# adsr2.net
KiCad netlist of a schematic drawn in EAGLE
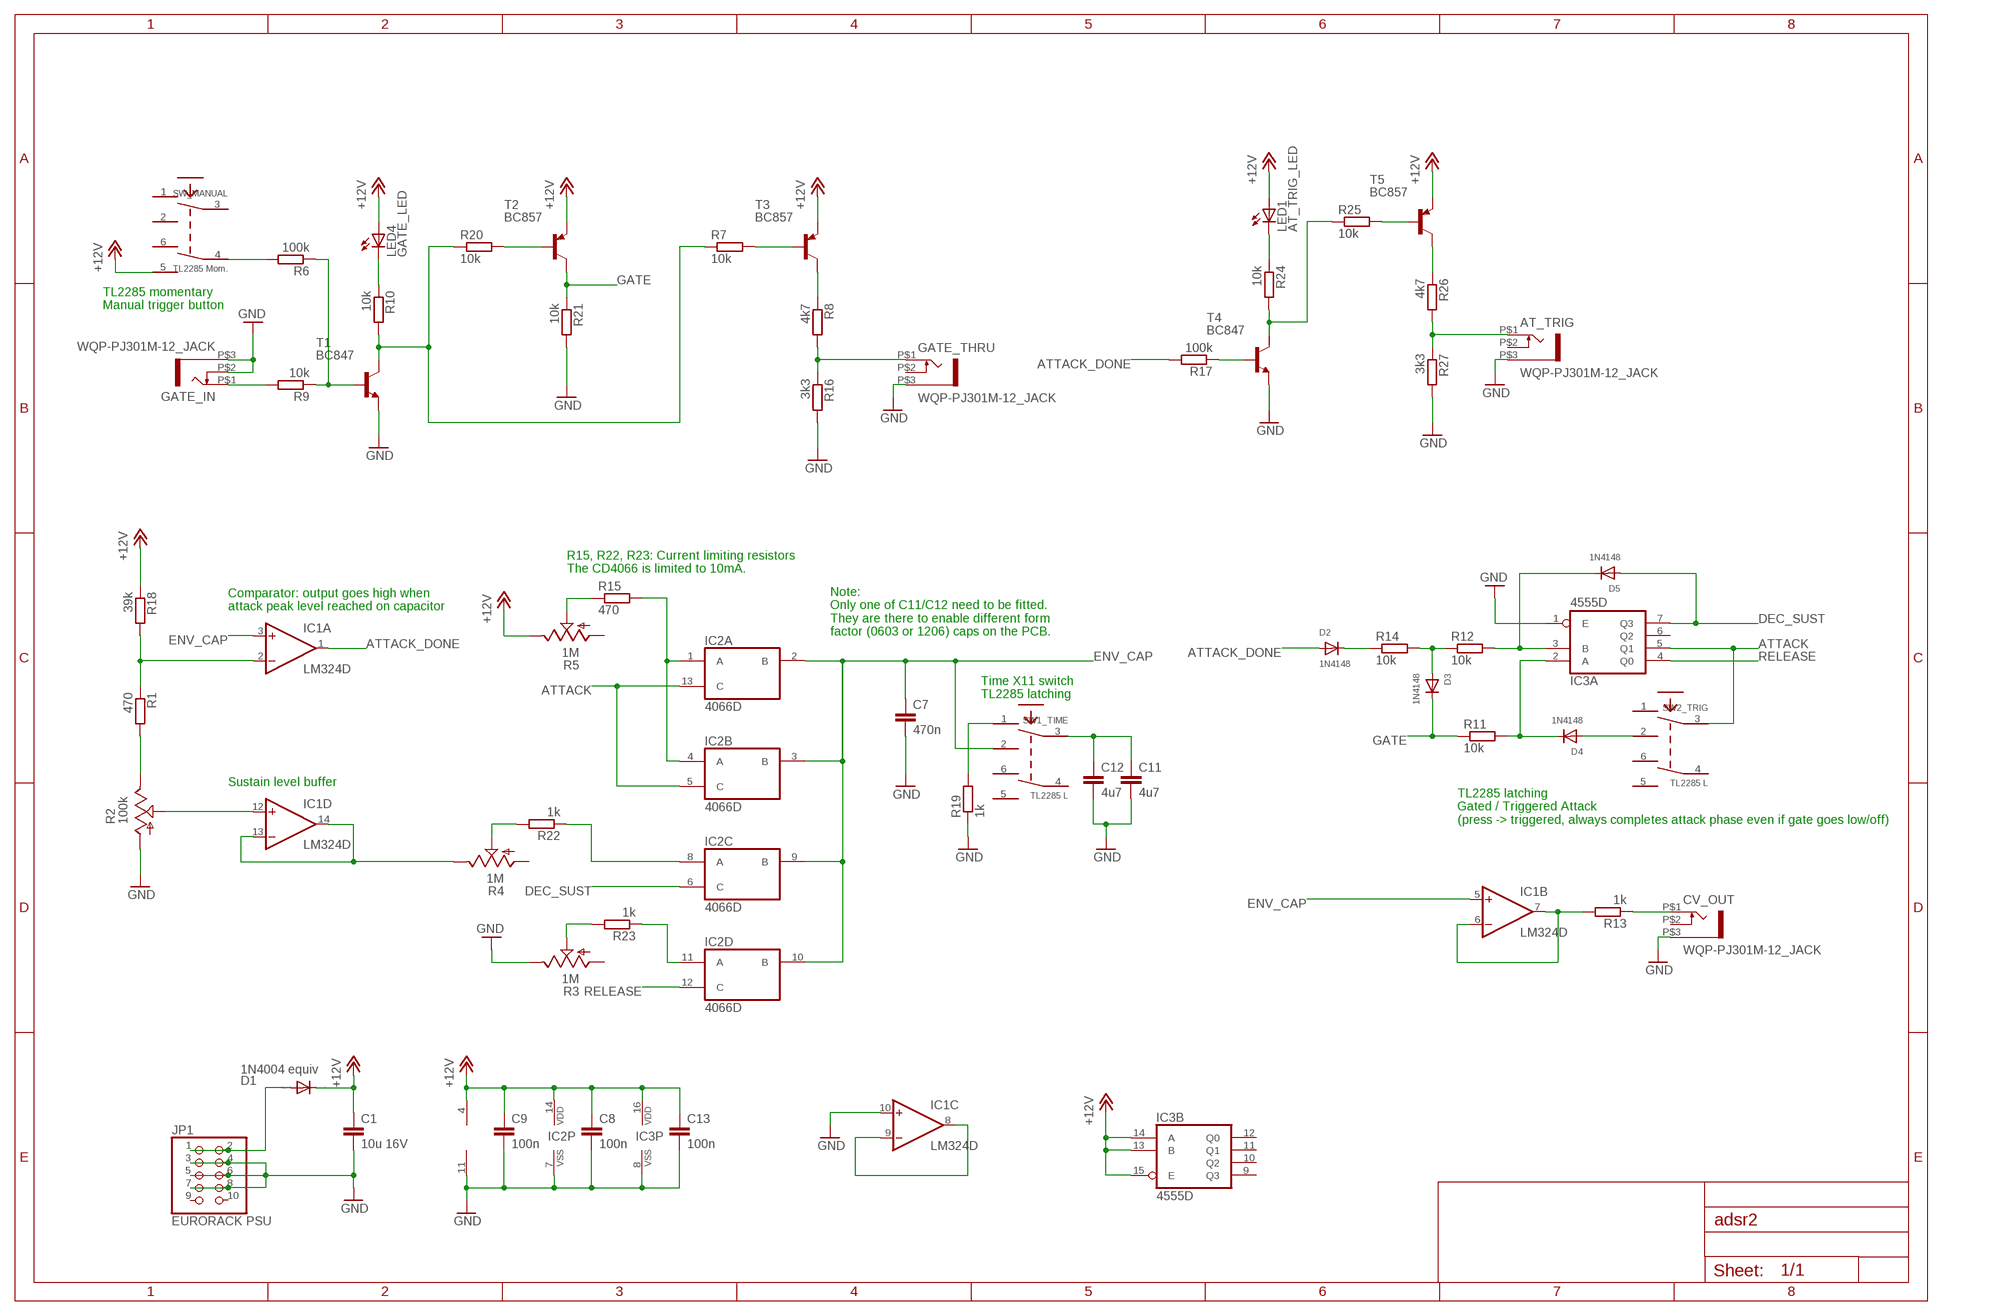
[diagram p0: schematic, sheet 1]

(export (version "E")
  (design (tool "Eeschema 10.0.6"))
  (components
    (comp (ref "AT_TRIG")
      (value "WQP-PJ301M-12_JACK")
      (footprint "eagle-import:WQP-PJ301M-12_JACK")
      (libsource (lib "eagle-import") (part "WQP-PJ301M-12_JACK"))
    )
    (comp (ref "C1")
      (value "10u 16V")
      (footprint "eagle-import:C1206K")
      (libsource (lib "eagle-import") (part "C-EUC1206K"))
    )
    (comp (ref "C7")
      (value "470n")
      (footprint "eagle-import:C0603K")
      (libsource (lib "eagle-import") (part "C-EUC0603K"))
    )
    (comp (ref "C8")
      (value "100n")
      (footprint "eagle-import:C0603K")
      (libsource (lib "eagle-import") (part "C-EUC0603K"))
    )
    (comp (ref "C9")
      (value "100n")
      (footprint "eagle-import:C0603K")
      (libsource (lib "eagle-import") (part "C-EUC0603K"))
    )
    (comp (ref "C11")
      (value "4u7")
      (footprint "eagle-import:C1206K")
      (libsource (lib "eagle-import") (part "C-EUC1206K"))
    )
    (comp (ref "C12")
      (value "4u7")
      (footprint "eagle-import:C0603K")
      (libsource (lib "eagle-import") (part "C-EUC0603K"))
    )
    (comp (ref "C13")
      (value "100n")
      (footprint "eagle-import:C0603K")
      (libsource (lib "eagle-import") (part "C-EUC0603K"))
    )
    (comp (ref "CV_OUT")
      (value "WQP-PJ301M-12_JACK")
      (footprint "eagle-import:WQP-PJ301M-12_JACK")
      (libsource (lib "eagle-import") (part "WQP-PJ301M-12_JACK"))
    )
    (comp (ref "D1")
      (value "1N4004 equiv")
      (footprint "eagle-import:DO214AA")
      (libsource (lib "eagle-import") (part "DIODE-DO214AA"))
    )
    (comp (ref "D2")
      (value "1N4148")
      (footprint "eagle-import:SOD-323F")
      (libsource (lib "eagle-import") (part "DIODESOD-323F"))
    )
    (comp (ref "D3")
      (value "1N4148")
      (footprint "eagle-import:SOD-323F")
      (libsource (lib "eagle-import") (part "DIODESOD-323F"))
    )
    (comp (ref "D4")
      (value "1N4148")
      (footprint "eagle-import:SOD-323F")
      (libsource (lib "eagle-import") (part "DIODESOD-323F"))
    )
    (comp (ref "D5")
      (value "1N4148")
      (footprint "eagle-import:SOD-323F")
      (libsource (lib "eagle-import") (part "DIODESOD-323F"))
    )
    (comp (ref "GATE_IN")
      (value "WQP-PJ301M-12_JACK")
      (footprint "eagle-import:WQP-PJ301M-12_JACK")
      (libsource (lib "eagle-import") (part "WQP-PJ301M-12_JACK"))
    )
    (comp (ref "GATE_THRU")
      (value "WQP-PJ301M-12_JACK")
      (footprint "eagle-import:WQP-PJ301M-12_JACK")
      (libsource (lib "eagle-import") (part "WQP-PJ301M-12_JACK"))
    )
    (comp (ref "IC1")
      (value "LM324D")
      (footprint "eagle-import:SO14")
      (libsource (lib "eagle-import") (part "LM324D"))
    )
    (comp (ref "IC2")
      (value "4066D")
      (footprint "eagle-import:SO14")
      (libsource (lib "eagle-import") (part "4066D"))
    )
    (comp (ref "IC3")
      (value "4555D")
      (footprint "eagle-import:SO16")
      (libsource (lib "eagle-import") (part "4555D"))
    )
    (comp (ref "JP1")
      (value "EURORACK PSU")
      (footprint "eagle-import:2X05")
      (libsource (lib "eagle-import") (part "PINHD-2X5"))
    )
    (comp (ref "LED1")
      (value "AT_TRIG_LED")
      (footprint "eagle-import:LED3MM")
      (libsource (lib "eagle-import") (part "LED3MM"))
    )
    (comp (ref "LED4")
      (value "GATE_LED")
      (footprint "eagle-import:LED3MM")
      (libsource (lib "eagle-import") (part "LED3MM"))
    )
    (comp (ref "R1")
      (value "470")
      (footprint "eagle-import:R0603")
      (libsource (lib "eagle-import") (part "R-EU_R0603"))
    )
    (comp (ref "R2")
      (value "100k")
      (footprint "eagle-import:ALPS_POT_VERTICAL")
      (libsource (lib "eagle-import") (part "POT_USVERTICAL"))
    )
    (comp (ref "R3")
      (value "1M")
      (footprint "eagle-import:ALPS_POT_VERTICAL")
      (libsource (lib "eagle-import") (part "POT_USVERTICAL"))
    )
    (comp (ref "R4")
      (value "1M")
      (footprint "eagle-import:ALPS_POT_VERTICAL")
      (libsource (lib "eagle-import") (part "POT_USVERTICAL"))
    )
    (comp (ref "R5")
      (value "1M")
      (footprint "eagle-import:ALPS_POT_VERTICAL")
      (libsource (lib "eagle-import") (part "POT_USVERTICAL"))
    )
    (comp (ref "R6")
      (value "100k")
      (footprint "eagle-import:R0603")
      (libsource (lib "eagle-import") (part "R-EU_R0603"))
    )
    (comp (ref "R7")
      (value "10k")
      (footprint "eagle-import:R0603")
      (libsource (lib "eagle-import") (part "R-EU_R0603"))
    )
    (comp (ref "R8")
      (value "4k7")
      (footprint "eagle-import:R0603")
      (libsource (lib "eagle-import") (part "R-EU_R0603"))
    )
    (comp (ref "R9")
      (value "10k")
      (footprint "eagle-import:R0603")
      (libsource (lib "eagle-import") (part "R-EU_R0603"))
    )
    (comp (ref "R10")
      (value "10k")
      (footprint "eagle-import:R0603")
      (libsource (lib "eagle-import") (part "R-EU_R0603"))
    )
    (comp (ref "R11")
      (value "10k")
      (footprint "eagle-import:R0603")
      (libsource (lib "eagle-import") (part "R-EU_R0603"))
    )
    (comp (ref "R12")
      (value "10k")
      (footprint "eagle-import:R0603")
      (libsource (lib "eagle-import") (part "R-EU_R0603"))
    )
    (comp (ref "R13")
      (value "1k")
      (footprint "eagle-import:R0603")
      (libsource (lib "eagle-import") (part "R-EU_R0603"))
    )
    (comp (ref "R14")
      (value "10k")
      (footprint "eagle-import:R0603")
      (libsource (lib "eagle-import") (part "R-EU_R0603"))
    )
    (comp (ref "R15")
      (value "470")
      (footprint "eagle-import:R0603")
      (libsource (lib "eagle-import") (part "R-EU_R0603"))
    )
    (comp (ref "R16")
      (value "3k3")
      (footprint "eagle-import:R0603")
      (libsource (lib "eagle-import") (part "R-EU_R0603"))
    )
    (comp (ref "R17")
      (value "100k")
      (footprint "eagle-import:R0603")
      (libsource (lib "eagle-import") (part "R-EU_R0603"))
    )
    (comp (ref "R18")
      (value "39k")
      (footprint "eagle-import:R0603")
      (libsource (lib "eagle-import") (part "R-EU_R0603"))
    )
    (comp (ref "R19")
      (value "1k")
      (footprint "eagle-import:R0603")
      (libsource (lib "eagle-import") (part "R-EU_R0603"))
    )
    (comp (ref "R20")
      (value "10k")
      (footprint "eagle-import:R0603")
      (libsource (lib "eagle-import") (part "R-EU_R0603"))
    )
    (comp (ref "R21")
      (value "10k")
      (footprint "eagle-import:R0603")
      (libsource (lib "eagle-import") (part "R-EU_R0603"))
    )
    (comp (ref "R22")
      (value "1k")
      (footprint "eagle-import:R0603")
      (libsource (lib "eagle-import") (part "R-EU_R0603"))
    )
    (comp (ref "R23")
      (value "1k")
      (footprint "eagle-import:R0603")
      (libsource (lib "eagle-import") (part "R-EU_R0603"))
    )
    (comp (ref "R24")
      (value "10k")
      (footprint "eagle-import:R0603")
      (libsource (lib "eagle-import") (part "R-EU_R0603"))
    )
    (comp (ref "R25")
      (value "10k")
      (footprint "eagle-import:R0603")
      (libsource (lib "eagle-import") (part "R-EU_R0603"))
    )
    (comp (ref "R26")
      (value "4k7")
      (footprint "eagle-import:R0603")
      (libsource (lib "eagle-import") (part "R-EU_R0603"))
    )
    (comp (ref "R27")
      (value "3k3")
      (footprint "eagle-import:R0603")
      (libsource (lib "eagle-import") (part "R-EU_R0603"))
    )
    (comp (ref "SW1_TIME")
      (value "TL2285 L")
      (footprint "eagle-import:TL2285_PCB")
      (libsource (lib "eagle-import") (part "TL2285"))
    )
    (comp (ref "SW2_TRIG")
      (value "TL2285 L")
      (footprint "eagle-import:TL2285_PCB")
      (libsource (lib "eagle-import") (part "TL2285"))
    )
    (comp (ref "SW_MANUAL")
      (value "TL2285 Mom.")
      (footprint "eagle-import:TL2285_PCB")
      (libsource (lib "eagle-import") (part "TL2285"))
    )
    (comp (ref "T1")
      (value "BC847")
      (footprint "eagle-import:SOT23")
      (libsource (lib "eagle-import") (part "BC847"))
    )
    (comp (ref "T2")
      (value "BC857")
      (footprint "eagle-import:SOT23-BEC")
      (libsource (lib "eagle-import") (part "-PNP-SOT23-BECBC857A"))
    )
    (comp (ref "T3")
      (value "BC857")
      (footprint "eagle-import:SOT23-BEC")
      (libsource (lib "eagle-import") (part "-PNP-SOT23-BECBC857A"))
    )
    (comp (ref "T4")
      (value "BC847")
      (footprint "eagle-import:SOT23")
      (libsource (lib "eagle-import") (part "BC847"))
    )
    (comp (ref "T5")
      (value "BC857")
      (footprint "eagle-import:SOT23-BEC")
      (libsource (lib "eagle-import") (part "-PNP-SOT23-BECBC857A"))
    )
  )
  (nets
    (net (code "1") (name "+12V") (class "Default")
      (node (ref "C1") (pin "1") (pinfunction "1_1") (pintype "passive"))
      (node (ref "C13") (pin "1") (pinfunction "1_1") (pintype "passive"))
      (node (ref "C8") (pin "1") (pinfunction "1_1") (pintype "passive"))
      (node (ref "C9") (pin "1") (pinfunction "1_1") (pintype "passive"))
      (node (ref "D1") (pin "C") (pinfunction "C_C") (pintype "passive"))
      (node (ref "IC1") (pin "4") (pinfunction "V+_4") (pintype "power_in"))
      (node (ref "IC2") (pin "14") (pinfunction "VDD_14") (pintype "power_in"))
      (node (ref "IC3") (pin "13") (pinfunction "B_13") (pintype "input"))
      (node (ref "IC3") (pin "14") (pinfunction "A_14") (pintype "input"))
      (node (ref "IC3") (pin "15") (pinfunction "E_15") (pintype "input"))
      (node (ref "IC3") (pin "16") (pinfunction "VDD_16") (pintype "power_in"))
      (node (ref "LED1") (pin "A") (pinfunction "A_A") (pintype "passive"))
      (node (ref "LED4") (pin "A") (pinfunction "A_A") (pintype "passive"))
      (node (ref "R18") (pin "1") (pinfunction "1_1") (pintype "passive"))
      (node (ref "R5") (pin "P$1") (pinfunction "E_P$1") (pintype "passive"))
      (node (ref "SW_MANUAL") (pin "5") (pinfunction "P5_5") (pintype "bidirectional"))
      (node (ref "T2") (pin "E") (pinfunction "E_E") (pintype "passive"))
      (node (ref "T3") (pin "E") (pinfunction "E_E") (pintype "passive"))
      (node (ref "T5") (pin "E") (pinfunction "E_E") (pintype "passive"))
    )
    (net (code "2") (name "/ATTACK") (class "Default")
      (node (ref "IC2") (pin "13") (pinfunction "C_13") (pintype "input"))
      (node (ref "IC2") (pin "5") (pinfunction "C_5") (pintype "input"))
      (node (ref "IC3") (pin "5") (pinfunction "Q1_5") (pintype "output"))
      (node (ref "SW2_TRIG") (pin "3") (pinfunction "P3_3") (pintype "bidirectional"))
    )
    (net (code "3") (name "/ATTACK_DONE") (class "Default")
      (node (ref "D2") (pin "A") (pinfunction "A_A") (pintype "passive"))
      (node (ref "IC1") (pin "1") (pinfunction "OUT_1") (pintype "output"))
      (node (ref "R17") (pin "2") (pinfunction "2_2") (pintype "passive"))
    )
    (net (code "4") (name "/DEC_SUST") (class "Default")
      (node (ref "D5") (pin "A") (pinfunction "A_A") (pintype "passive"))
      (node (ref "IC2") (pin "6") (pinfunction "C_6") (pintype "input"))
      (node (ref "IC3") (pin "7") (pinfunction "Q3_7") (pintype "output"))
    )
    (net (code "5") (name "/ENV_CAP") (class "Default")
      (node (ref "C7") (pin "1") (pinfunction "1_1") (pintype "passive"))
      (node (ref "IC1") (pin "3") (pinfunction "+IN_3") (pintype "input"))
      (node (ref "IC1") (pin "5") (pinfunction "+IN_5") (pintype "input"))
      (node (ref "IC2") (pin "10") (pinfunction "B_10") (pintype "tri_state"))
      (node (ref "IC2") (pin "2") (pinfunction "B_2") (pintype "tri_state"))
      (node (ref "IC2") (pin "3") (pinfunction "B_3") (pintype "tri_state"))
      (node (ref "IC2") (pin "9") (pinfunction "B_9") (pintype "tri_state"))
      (node (ref "SW1_TIME") (pin "2") (pinfunction "P2_2") (pintype "bidirectional"))
    )
    (net (code "6") (name "/GATE") (class "Default")
      (node (ref "D3") (pin "C") (pinfunction "C_C") (pintype "passive"))
      (node (ref "R11") (pin "1") (pinfunction "1_1") (pintype "passive"))
      (node (ref "R21") (pin "1") (pinfunction "1_1") (pintype "passive"))
      (node (ref "T2") (pin "C") (pinfunction "C_C") (pintype "passive"))
    )
    (net (code "7") (name "/RELEASE") (class "Default")
      (node (ref "IC2") (pin "12") (pinfunction "C_12") (pintype "input"))
      (node (ref "IC3") (pin "4") (pinfunction "Q0_4") (pintype "output"))
    )
    (net (code "8") (name "GND") (class "Default")
      (node (ref "AT_TRIG") (pin "P$3") (pinfunction "1_P$3") (pintype "passive"))
      (node (ref "C1") (pin "2") (pinfunction "2_2") (pintype "passive"))
      (node (ref "C11") (pin "2") (pinfunction "2_2") (pintype "passive"))
      (node (ref "C12") (pin "2") (pinfunction "2_2") (pintype "passive"))
      (node (ref "C13") (pin "2") (pinfunction "2_2") (pintype "passive"))
      (node (ref "C7") (pin "2") (pinfunction "2_2") (pintype "passive"))
      (node (ref "C8") (pin "2") (pinfunction "2_2") (pintype "passive"))
      (node (ref "C9") (pin "2") (pinfunction "2_2") (pintype "passive"))
      (node (ref "CV_OUT") (pin "P$3") (pinfunction "1_P$3") (pintype "passive"))
      (node (ref "GATE_IN") (pin "P$2") (pinfunction "3_P$2") (pintype "passive"))
      (node (ref "GATE_IN") (pin "P$3") (pinfunction "1_P$3") (pintype "passive"))
      (node (ref "GATE_THRU") (pin "P$3") (pinfunction "1_P$3") (pintype "passive"))
      (node (ref "IC1") (pin "10") (pinfunction "+IN_10") (pintype "input"))
      (node (ref "IC1") (pin "11") (pinfunction "V-_11") (pintype "power_in"))
      (node (ref "IC2") (pin "7") (pinfunction "VSS_7") (pintype "power_in"))
      (node (ref "IC3") (pin "1") (pinfunction "E_1") (pintype "input"))
      (node (ref "IC3") (pin "8") (pinfunction "VSS_8") (pintype "power_in"))
      (node (ref "JP1") (pin "3") (pinfunction "3_3") (pintype "passive"))
      (node (ref "JP1") (pin "4") (pinfunction "4_4") (pintype "passive"))
      (node (ref "JP1") (pin "5") (pinfunction "5_5") (pintype "passive"))
      (node (ref "JP1") (pin "6") (pinfunction "6_6") (pintype "passive"))
      (node (ref "JP1") (pin "7") (pinfunction "7_7") (pintype "passive"))
      (node (ref "JP1") (pin "8") (pinfunction "8_8") (pintype "passive"))
      (node (ref "R16") (pin "2") (pinfunction "2_2") (pintype "passive"))
      (node (ref "R19") (pin "1") (pinfunction "1_1") (pintype "passive"))
      (node (ref "R2") (pin "P$3") (pinfunction "A_P$3") (pintype "passive"))
      (node (ref "R21") (pin "2") (pinfunction "2_2") (pintype "passive"))
      (node (ref "R27") (pin "2") (pinfunction "2_2") (pintype "passive"))
      (node (ref "R3") (pin "P$1") (pinfunction "E_P$1") (pintype "passive"))
      (node (ref "T1") (pin "2") (pinfunction "E_2") (pintype "passive"))
      (node (ref "T4") (pin "2") (pinfunction "E_2") (pintype "passive"))
    )
    (net (code "9") (name "Net-(AT_TRIG-2)") (class "Default")
      (node (ref "AT_TRIG") (pin "P$1") (pinfunction "2_P$1") (pintype "passive"))
      (node (ref "R26") (pin "2") (pinfunction "2_2") (pintype "passive"))
      (node (ref "R27") (pin "1") (pinfunction "1_1") (pintype "passive"))
    )
    (net (code "10") (name "Net-(CV_OUT-2)") (class "Default")
      (node (ref "CV_OUT") (pin "P$1") (pinfunction "2_P$1") (pintype "passive"))
      (node (ref "R13") (pin "1") (pinfunction "1_1") (pintype "passive"))
    )
    (net (code "11") (name "Net-(D1-PadA)") (class "Default")
      (node (ref "D1") (pin "A") (pinfunction "A_A") (pintype "passive"))
      (node (ref "JP1") (pin "1") (pinfunction "1_1") (pintype "passive"))
      (node (ref "JP1") (pin "2") (pinfunction "2_2") (pintype "passive"))
    )
    (net (code "12") (name "Net-(D2-PadC)") (class "Default")
      (node (ref "D2") (pin "C") (pinfunction "C_C") (pintype "passive"))
      (node (ref "R14") (pin "1") (pinfunction "1_1") (pintype "passive"))
    )
    (net (code "13") (name "Net-(D3-PadA)") (class "Default")
      (node (ref "D3") (pin "A") (pinfunction "A_A") (pintype "passive"))
      (node (ref "R12") (pin "1") (pinfunction "1_1") (pintype "passive"))
      (node (ref "R14") (pin "2") (pinfunction "2_2") (pintype "passive"))
    )
    (net (code "14") (name "Net-(GATE_IN-2)") (class "Default")
      (node (ref "GATE_IN") (pin "P$1") (pinfunction "2_P$1") (pintype "passive"))
      (node (ref "R9") (pin "2") (pinfunction "2_2") (pintype "passive"))
    )
    (net (code "15") (name "Net-(GATE_THRU-2)") (class "Default")
      (node (ref "GATE_THRU") (pin "P$1") (pinfunction "2_P$1") (pintype "passive"))
      (node (ref "R16") (pin "1") (pinfunction "1_1") (pintype "passive"))
      (node (ref "R8") (pin "2") (pinfunction "2_2") (pintype "passive"))
    )
    (net (code "16") (name "Net-(IC1A--IN)") (class "Default")
      (node (ref "IC1") (pin "2") (pinfunction "-IN_2") (pintype "input"))
      (node (ref "R1") (pin "1") (pinfunction "1_1") (pintype "passive"))
      (node (ref "R18") (pin "2") (pinfunction "2_2") (pintype "passive"))
    )
    (net (code "17") (name "Net-(IC1B--IN)") (class "Default")
      (node (ref "IC1") (pin "6") (pinfunction "-IN_6") (pintype "input"))
      (node (ref "IC1") (pin "7") (pinfunction "OUT_7") (pintype "output"))
      (node (ref "R13") (pin "2") (pinfunction "2_2") (pintype "passive"))
    )
    (net (code "18") (name "Net-(IC1C--IN)") (class "Default")
      (node (ref "IC1") (pin "8") (pinfunction "OUT_8") (pintype "output"))
      (node (ref "IC1") (pin "9") (pinfunction "-IN_9") (pintype "input"))
    )
    (net (code "19") (name "Net-(IC1D-+IN)") (class "Default")
      (node (ref "IC1") (pin "12") (pinfunction "+IN_12") (pintype "input"))
      (node (ref "R2") (pin "P$2") (pinfunction "S_P$2") (pintype "passive"))
    )
    (net (code "20") (name "Net-(IC1D--IN)") (class "Default")
      (node (ref "IC1") (pin "13") (pinfunction "-IN_13") (pintype "input"))
      (node (ref "IC1") (pin "14") (pinfunction "OUT_14") (pintype "output"))
      (node (ref "R4") (pin "P$1") (pinfunction "E_P$1") (pintype "passive"))
    )
    (net (code "21") (name "Net-(IC2A-A)") (class "Default")
      (node (ref "IC2") (pin "1") (pinfunction "A_1") (pintype "tri_state"))
      (node (ref "IC2") (pin "4") (pinfunction "A_4") (pintype "tri_state"))
      (node (ref "R15") (pin "2") (pinfunction "2_2") (pintype "passive"))
    )
    (net (code "22") (name "Net-(IC2C-A)") (class "Default")
      (node (ref "IC2") (pin "8") (pinfunction "A_8") (pintype "tri_state"))
      (node (ref "R22") (pin "1") (pinfunction "1_1") (pintype "passive"))
    )
    (net (code "23") (name "Net-(IC2D-A)") (class "Default")
      (node (ref "IC2") (pin "11") (pinfunction "A_11") (pintype "tri_state"))
      (node (ref "R23") (pin "1") (pinfunction "1_1") (pintype "passive"))
    )
    (net (code "24") (name "Net-(IC3A-A)") (class "Default")
      (node (ref "D4") (pin "C") (pinfunction "C_C") (pintype "passive"))
      (node (ref "IC3") (pin "2") (pinfunction "A_2") (pintype "input"))
      (node (ref "R11") (pin "2") (pinfunction "2_2") (pintype "passive"))
    )
    (net (code "25") (name "Net-(IC3A-B)") (class "Default")
      (node (ref "D5") (pin "C") (pinfunction "C_C") (pintype "passive"))
      (node (ref "IC3") (pin "3") (pinfunction "B_3") (pintype "input"))
      (node (ref "R12") (pin "2") (pinfunction "2_2") (pintype "passive"))
    )
    (net (code "26") (name "Net-(LED1-C)") (class "Default")
      (node (ref "LED1") (pin "K") (pinfunction "C_K") (pintype "passive"))
      (node (ref "R24") (pin "1") (pinfunction "1_1") (pintype "passive"))
    )
    (net (code "27") (name "Net-(LED4-C)") (class "Default")
      (node (ref "LED4") (pin "K") (pinfunction "C_K") (pintype "passive"))
      (node (ref "R10") (pin "1") (pinfunction "1_1") (pintype "passive"))
    )
    (net (code "28") (name "Net-(R2-E)") (class "Default")
      (node (ref "R1") (pin "2") (pinfunction "2_2") (pintype "passive"))
      (node (ref "R2") (pin "P$1") (pinfunction "E_P$1") (pintype "passive"))
    )
    (net (code "29") (name "Net-(R3-S)") (class "Default")
      (node (ref "R23") (pin "2") (pinfunction "2_2") (pintype "passive"))
      (node (ref "R3") (pin "P$2") (pinfunction "S_P$2") (pintype "passive"))
    )
    (net (code "30") (name "Net-(R4-S)") (class "Default")
      (node (ref "R22") (pin "2") (pinfunction "2_2") (pintype "passive"))
      (node (ref "R4") (pin "P$2") (pinfunction "S_P$2") (pintype "passive"))
    )
    (net (code "31") (name "Net-(R5-S)") (class "Default")
      (node (ref "R15") (pin "1") (pinfunction "1_1") (pintype "passive"))
      (node (ref "R5") (pin "P$2") (pinfunction "S_P$2") (pintype "passive"))
    )
    (net (code "32") (name "Net-(R7-Pad2)") (class "Default")
      (node (ref "R7") (pin "2") (pinfunction "2_2") (pintype "passive"))
      (node (ref "T3") (pin "B") (pinfunction "B_B") (pintype "passive"))
    )
    (net (code "33") (name "Net-(R8-Pad1)") (class "Default")
      (node (ref "R8") (pin "1") (pinfunction "1_1") (pintype "passive"))
      (node (ref "T3") (pin "C") (pinfunction "C_C") (pintype "passive"))
    )
    (net (code "34") (name "Net-(R20-Pad2)") (class "Default")
      (node (ref "R20") (pin "2") (pinfunction "2_2") (pintype "passive"))
      (node (ref "T2") (pin "B") (pinfunction "B_B") (pintype "passive"))
    )
    (net (code "35") (name "Net-(R25-Pad2)") (class "Default")
      (node (ref "R25") (pin "2") (pinfunction "2_2") (pintype "passive"))
      (node (ref "T5") (pin "B") (pinfunction "B_B") (pintype "passive"))
    )
    (net (code "36") (name "Net-(R26-Pad1)") (class "Default")
      (node (ref "R26") (pin "1") (pinfunction "1_1") (pintype "passive"))
      (node (ref "T5") (pin "C") (pinfunction "C_C") (pintype "passive"))
    )
    (net (code "37") (name "Net-(SW1_TIME-P1)") (class "Default")
      (node (ref "R19") (pin "2") (pinfunction "2_2") (pintype "passive"))
      (node (ref "SW1_TIME") (pin "1") (pinfunction "P1_1") (pintype "bidirectional"))
    )
    (net (code "38") (name "Net-(SW1_TIME-P3)") (class "Default")
      (node (ref "C11") (pin "1") (pinfunction "1_1") (pintype "passive"))
      (node (ref "C12") (pin "1") (pinfunction "1_1") (pintype "passive"))
      (node (ref "SW1_TIME") (pin "3") (pinfunction "P3_3") (pintype "bidirectional"))
    )
    (net (code "39") (name "Net-(SW2_TRIG-P2)") (class "Default")
      (node (ref "D4") (pin "A") (pinfunction "A_A") (pintype "passive"))
      (node (ref "SW2_TRIG") (pin "2") (pinfunction "P2_2") (pintype "bidirectional"))
    )
    (net (code "40") (name "Net-(SW_MANUAL-P4)") (class "Default")
      (node (ref "R6") (pin "2") (pinfunction "2_2") (pintype "passive"))
      (node (ref "SW_MANUAL") (pin "4") (pinfunction "P4_4") (pintype "bidirectional"))
    )
    (net (code "41") (name "Net-(T1-B)") (class "Default")
      (node (ref "R6") (pin "1") (pinfunction "1_1") (pintype "passive"))
      (node (ref "R9") (pin "1") (pinfunction "1_1") (pintype "passive"))
      (node (ref "T1") (pin "1") (pinfunction "B_1") (pintype "passive"))
    )
    (net (code "42") (name "Net-(T1-C)") (class "Default")
      (node (ref "R10") (pin "2") (pinfunction "2_2") (pintype "passive"))
      (node (ref "R20") (pin "1") (pinfunction "1_1") (pintype "passive"))
      (node (ref "R7") (pin "1") (pinfunction "1_1") (pintype "passive"))
      (node (ref "T1") (pin "3") (pinfunction "C_3") (pintype "passive"))
    )
    (net (code "43") (name "Net-(T4-B)") (class "Default")
      (node (ref "R17") (pin "1") (pinfunction "1_1") (pintype "passive"))
      (node (ref "T4") (pin "1") (pinfunction "B_1") (pintype "passive"))
    )
    (net (code "44") (name "Net-(T4-C)") (class "Default")
      (node (ref "R24") (pin "2") (pinfunction "2_2") (pintype "passive"))
      (node (ref "R25") (pin "1") (pinfunction "1_1") (pintype "passive"))
      (node (ref "T4") (pin "3") (pinfunction "C_3") (pintype "passive"))
    )
    (net (code "45") (name "unconnected-(AT_TRIG-3-PadP$2)") (class "Default")
      (node (ref "AT_TRIG") (pin "P$2") (pinfunction "3_P$2") (pintype "passive"))
    )
    (net (code "46") (name "unconnected-(CV_OUT-3-PadP$2)") (class "Default")
      (node (ref "CV_OUT") (pin "P$2") (pinfunction "3_P$2") (pintype "passive"))
    )
    (net (code "47") (name "unconnected-(GATE_THRU-3-PadP$2)") (class "Default")
      (node (ref "GATE_THRU") (pin "P$2") (pinfunction "3_P$2") (pintype "passive"))
    )
    (net (code "48") (name "unconnected-(IC3A-Q2-Pad6)") (class "Default")
      (node (ref "IC3") (pin "6") (pinfunction "Q2_6") (pintype "output"))
    )
    (net (code "49") (name "unconnected-(IC3B-Q0-Pad12)") (class "Default")
      (node (ref "IC3") (pin "12") (pinfunction "Q0_12") (pintype "output"))
    )
    (net (code "50") (name "unconnected-(IC3B-Q1-Pad11)") (class "Default")
      (node (ref "IC3") (pin "11") (pinfunction "Q1_11") (pintype "output"))
    )
    (net (code "51") (name "unconnected-(IC3B-Q2-Pad10)") (class "Default")
      (node (ref "IC3") (pin "10") (pinfunction "Q2_10") (pintype "output"))
    )
    (net (code "52") (name "unconnected-(IC3B-Q3-Pad9)") (class "Default")
      (node (ref "IC3") (pin "9") (pinfunction "Q3_9") (pintype "output"))
    )
    (net (code "53") (name "unconnected-(JP1-Pad9)") (class "Default")
      (node (ref "JP1") (pin "9") (pinfunction "9_9") (pintype "passive"))
    )
    (net (code "54") (name "unconnected-(JP1-Pad10)") (class "Default")
      (node (ref "JP1") (pin "10") (pinfunction "10_10") (pintype "passive"))
    )
    (net (code "55") (name "unconnected-(R3-A-PadP$3)") (class "Default")
      (node (ref "R3") (pin "P$3") (pinfunction "A_P$3") (pintype "passive"))
    )
    (net (code "56") (name "unconnected-(R4-A-PadP$3)") (class "Default")
      (node (ref "R4") (pin "P$3") (pinfunction "A_P$3") (pintype "passive"))
    )
    (net (code "57") (name "unconnected-(R5-A-PadP$3)") (class "Default")
      (node (ref "R5") (pin "P$3") (pinfunction "A_P$3") (pintype "passive"))
    )
    (net (code "58") (name "unconnected-(SW1_TIME-P4-Pad4)") (class "Default")
      (node (ref "SW1_TIME") (pin "4") (pinfunction "P4_4") (pintype "bidirectional"))
    )
    (net (code "59") (name "unconnected-(SW1_TIME-P5-Pad5)") (class "Default")
      (node (ref "SW1_TIME") (pin "5") (pinfunction "P5_5") (pintype "bidirectional"))
    )
    (net (code "60") (name "unconnected-(SW1_TIME-P6-Pad6)") (class "Default")
      (node (ref "SW1_TIME") (pin "6") (pinfunction "P6_6") (pintype "bidirectional"))
    )
    (net (code "61") (name "unconnected-(SW2_TRIG-P1-Pad1)") (class "Default")
      (node (ref "SW2_TRIG") (pin "1") (pinfunction "P1_1") (pintype "bidirectional"))
    )
    (net (code "62") (name "unconnected-(SW2_TRIG-P4-Pad4)") (class "Default")
      (node (ref "SW2_TRIG") (pin "4") (pinfunction "P4_4") (pintype "bidirectional"))
    )
    (net (code "63") (name "unconnected-(SW2_TRIG-P5-Pad5)") (class "Default")
      (node (ref "SW2_TRIG") (pin "5") (pinfunction "P5_5") (pintype "bidirectional"))
    )
    (net (code "64") (name "unconnected-(SW2_TRIG-P6-Pad6)") (class "Default")
      (node (ref "SW2_TRIG") (pin "6") (pinfunction "P6_6") (pintype "bidirectional"))
    )
    (net (code "65") (name "unconnected-(SW_MANUAL-P1-Pad1)") (class "Default")
      (node (ref "SW_MANUAL") (pin "1") (pinfunction "P1_1") (pintype "bidirectional"))
    )
    (net (code "66") (name "unconnected-(SW_MANUAL-P2-Pad2)") (class "Default")
      (node (ref "SW_MANUAL") (pin "2") (pinfunction "P2_2") (pintype "bidirectional"))
    )
    (net (code "67") (name "unconnected-(SW_MANUAL-P3-Pad3)") (class "Default")
      (node (ref "SW_MANUAL") (pin "3") (pinfunction "P3_3") (pintype "bidirectional"))
    )
    (net (code "68") (name "unconnected-(SW_MANUAL-P6-Pad6)") (class "Default")
      (node (ref "SW_MANUAL") (pin "6") (pinfunction "P6_6") (pintype "bidirectional"))
    )
  )
)
